# HammerHeadBreakout.net
KiCad netlist of a schematic drawn in Altium Designer
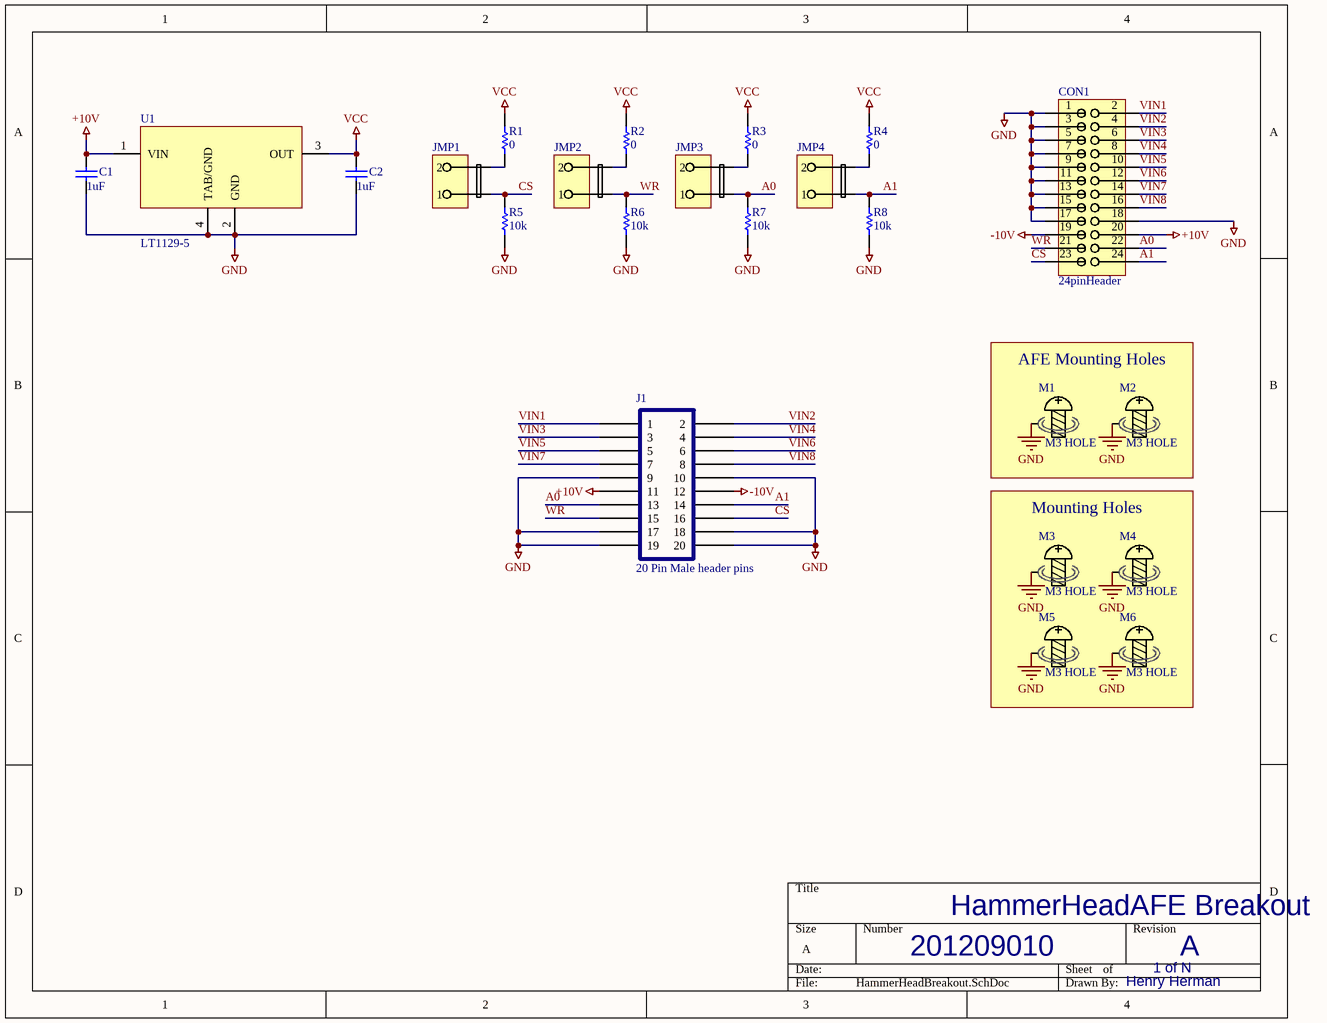
[diagram p0: HammerHeadBreakout.SchDoc]

(export (version "E")
  (design (tool "Eeschema 10.0.6"))
  (components
    (comp (ref "C1")
      (value "1uF")
      (footprint "SM/C_0805")
      (description "CAP")
      (libsource (lib "Henry1_20_2010") (part "CAP"))
    )
    (comp (ref "C2")
      (value "1uF")
      (footprint "SM/C_0805")
      (description "CAP")
      (libsource (lib "Henry1_20_2010") (part "CAP"))
    )
    (comp (ref "CON1")
      (value "24pinHeader")
      (footprint "CONN-RECEPT-24PIN")
      (libsource (lib "Henry1_20_2010") (part "24pinHeader"))
    )
    (comp (ref "J1")
      (value "20 Pin Male header pins")
      (footprint "M10x2-Shrouded")
      (description "Standard 20 Pin Ribbon Cable Connector")
      (libsource (lib "Henry1_20_2010") (part "M10x2-HeaderPinsConnector"))
    )
    (comp (ref "JMP1")
      (value "JMPR-2PIN-THRU")
      (footprint "M02")
      (libsource (lib "Henry1_20_2010") (part "JMPR-2PIN-THRU"))
    )
    (comp (ref "JMP2")
      (value "JMPR-2PIN-THRU")
      (footprint "M02")
      (libsource (lib "Henry1_20_2010") (part "JMPR-2PIN-THRU"))
    )
    (comp (ref "JMP3")
      (value "JMPR-2PIN-THRU")
      (footprint "M02")
      (libsource (lib "Henry1_20_2010") (part "JMPR-2PIN-THRU"))
    )
    (comp (ref "JMP4")
      (value "JMPR-2PIN-THRU")
      (footprint "M02")
      (libsource (lib "Henry1_20_2010") (part "JMPR-2PIN-THRU"))
    )
    (comp (ref "M1")
      (value "M3 HOLE")
      (footprint "MOUNTING_HOLE-125mil")
      (libsource (lib "Henry1_20_2010") (part "MountingHole"))
    )
    (comp (ref "M2")
      (value "M3 HOLE")
      (footprint "MOUNTING_HOLE-125mil")
      (libsource (lib "Henry1_20_2010") (part "MountingHole"))
    )
    (comp (ref "M3")
      (value "M3 HOLE")
      (footprint "MOUNTING_HOLE-125mil")
      (libsource (lib "Henry1_20_2010") (part "MountingHole"))
    )
    (comp (ref "M4")
      (value "M3 HOLE")
      (footprint "MOUNTING_HOLE-125mil")
      (libsource (lib "Henry1_20_2010") (part "MountingHole"))
    )
    (comp (ref "M5")
      (value "M3 HOLE")
      (footprint "MOUNTING_HOLE-125mil")
      (libsource (lib "Henry1_20_2010") (part "MountingHole"))
    )
    (comp (ref "M6")
      (value "M3 HOLE")
      (footprint "MOUNTING_HOLE-125mil")
      (libsource (lib "Henry1_20_2010") (part "MountingHole"))
    )
    (comp (ref "R1")
      (value "0")
      (footprint "SM/R_0805")
      (description "Resistor")
      (fields (field (name "Comment") "Res") (field (name "PUBLISHER") "Altium Limited"))
      (libsource (lib "Henry1_20_2010") (part "Res"))
    )
    (comp (ref "R2")
      (value "0")
      (footprint "SM/R_0805")
      (description "Resistor")
      (fields (field (name "Comment") "Res") (field (name "PUBLISHER") "Altium Limited"))
      (libsource (lib "Henry1_20_2010") (part "Res"))
    )
    (comp (ref "R3")
      (value "0")
      (footprint "SM/R_0805")
      (description "Resistor")
      (fields (field (name "Comment") "Res") (field (name "PUBLISHER") "Altium Limited"))
      (libsource (lib "Henry1_20_2010") (part "Res"))
    )
    (comp (ref "R4")
      (value "0")
      (footprint "SM/R_0805")
      (description "Resistor")
      (fields (field (name "Comment") "Res") (field (name "PUBLISHER") "Altium Limited"))
      (libsource (lib "Henry1_20_2010") (part "Res"))
    )
    (comp (ref "R5")
      (value "10k")
      (footprint "SM/R_0805")
      (description "Resistor")
      (fields (field (name "Comment") "Res") (field (name "PUBLISHER") "Altium Limited"))
      (libsource (lib "Henry1_20_2010") (part "Res"))
    )
    (comp (ref "R6")
      (value "10k")
      (footprint "SM/R_0805")
      (description "Resistor")
      (fields (field (name "Comment") "Res") (field (name "PUBLISHER") "Altium Limited"))
      (libsource (lib "Henry1_20_2010") (part "Res"))
    )
    (comp (ref "R7")
      (value "10k")
      (footprint "SM/R_0805")
      (description "Resistor")
      (fields (field (name "Comment") "Res") (field (name "PUBLISHER") "Altium Limited"))
      (libsource (lib "Henry1_20_2010") (part "Res"))
    )
    (comp (ref "R8")
      (value "10k")
      (footprint "SM/R_0805")
      (description "Resistor")
      (fields (field (name "Comment") "Res") (field (name "PUBLISHER") "Altium Limited"))
      (libsource (lib "Henry1_20_2010") (part "Res"))
    )
    (comp (ref "U1")
      (value "LT1129-5")
      (footprint "SOT223-3Lead-STPackage-LinearTechLT1129-3.3")
      (libsource (lib "Henry1_20_2010") (part "LT1129-5"))
    )
  )
  (nets
    (net (code "1") (name "+10V") (class "Default")
      (node (ref "C1") (pin "2") (pinfunction "2_2") (pintype "passive"))
      (node (ref "CON1") (pin "20") (pinfunction "20_20") (pintype "passive"))
      (node (ref "J1") (pin "11") (pinfunction "11_11") (pintype "passive"))
      (node (ref "U1") (pin "1") (pinfunction "VIN_1") (pintype "passive"))
    )
    (net (code "2") (name "-10V") (class "Default")
      (node (ref "CON1") (pin "19") (pinfunction "19_19") (pintype "passive"))
      (node (ref "J1") (pin "12") (pinfunction "12_12") (pintype "passive"))
    )
    (net (code "3") (name "/A0") (class "Default")
      (node (ref "CON1") (pin "22") (pinfunction "22_22") (pintype "passive"))
      (node (ref "J1") (pin "13") (pinfunction "13_13") (pintype "passive"))
      (node (ref "JMP3") (pin "1") (pinfunction "1_1") (pintype "passive"))
      (node (ref "R7") (pin "2") (pinfunction "2_2") (pintype "passive"))
    )
    (net (code "4") (name "/A1") (class "Default")
      (node (ref "CON1") (pin "24") (pinfunction "24_24") (pintype "passive"))
      (node (ref "J1") (pin "14") (pinfunction "14_14") (pintype "passive"))
      (node (ref "JMP4") (pin "1") (pinfunction "1_1") (pintype "passive"))
      (node (ref "R8") (pin "2") (pinfunction "2_2") (pintype "passive"))
    )
    (net (code "5") (name "/CS") (class "Default")
      (node (ref "CON1") (pin "23") (pinfunction "23_23") (pintype "passive"))
      (node (ref "J1") (pin "16") (pinfunction "16_16") (pintype "passive"))
      (node (ref "JMP1") (pin "1") (pinfunction "1_1") (pintype "passive"))
      (node (ref "R5") (pin "2") (pinfunction "2_2") (pintype "passive"))
    )
    (net (code "6") (name "/VIN1") (class "Default")
      (node (ref "CON1") (pin "2") (pinfunction "2_2") (pintype "passive"))
      (node (ref "J1") (pin "1") (pinfunction "1_1") (pintype "passive"))
    )
    (net (code "7") (name "/VIN2") (class "Default")
      (node (ref "CON1") (pin "4") (pinfunction "4_4") (pintype "passive"))
      (node (ref "J1") (pin "2") (pinfunction "2_2") (pintype "passive"))
    )
    (net (code "8") (name "/VIN3") (class "Default")
      (node (ref "CON1") (pin "6") (pinfunction "6_6") (pintype "passive"))
      (node (ref "J1") (pin "3") (pinfunction "3_3") (pintype "passive"))
    )
    (net (code "9") (name "/VIN4") (class "Default")
      (node (ref "CON1") (pin "8") (pinfunction "8_8") (pintype "passive"))
      (node (ref "J1") (pin "4") (pinfunction "4_4") (pintype "passive"))
    )
    (net (code "10") (name "/VIN5") (class "Default")
      (node (ref "CON1") (pin "10") (pinfunction "10_10") (pintype "passive"))
      (node (ref "J1") (pin "5") (pinfunction "5_5") (pintype "passive"))
    )
    (net (code "11") (name "/VIN6") (class "Default")
      (node (ref "CON1") (pin "12") (pinfunction "12_12") (pintype "passive"))
      (node (ref "J1") (pin "6") (pinfunction "6_6") (pintype "passive"))
    )
    (net (code "12") (name "/VIN7") (class "Default")
      (node (ref "CON1") (pin "14") (pinfunction "14_14") (pintype "passive"))
      (node (ref "J1") (pin "7") (pinfunction "7_7") (pintype "passive"))
    )
    (net (code "13") (name "/VIN8") (class "Default")
      (node (ref "CON1") (pin "16") (pinfunction "16_16") (pintype "passive"))
      (node (ref "J1") (pin "8") (pinfunction "8_8") (pintype "passive"))
    )
    (net (code "14") (name "/WR") (class "Default")
      (node (ref "CON1") (pin "21") (pinfunction "21_21") (pintype "passive"))
      (node (ref "J1") (pin "15") (pinfunction "15_15") (pintype "passive"))
      (node (ref "JMP2") (pin "1") (pinfunction "1_1") (pintype "passive"))
      (node (ref "R6") (pin "2") (pinfunction "2_2") (pintype "passive"))
    )
    (net (code "15") (name "GND") (class "Default")
      (node (ref "C1") (pin "1") (pinfunction "1_1") (pintype "passive"))
      (node (ref "C2") (pin "1") (pinfunction "1_1") (pintype "passive"))
      (node (ref "CON1") (pin "1") (pinfunction "1_1") (pintype "passive"))
      (node (ref "CON1") (pin "11") (pinfunction "11_11") (pintype "passive"))
      (node (ref "CON1") (pin "13") (pinfunction "13_13") (pintype "passive"))
      (node (ref "CON1") (pin "15") (pinfunction "15_15") (pintype "passive"))
      (node (ref "CON1") (pin "17") (pinfunction "17_17") (pintype "passive"))
      (node (ref "CON1") (pin "18") (pinfunction "18_18") (pintype "passive"))
      (node (ref "CON1") (pin "3") (pinfunction "3_3") (pintype "passive"))
      (node (ref "CON1") (pin "5") (pinfunction "5_5") (pintype "passive"))
      (node (ref "CON1") (pin "7") (pinfunction "7_7") (pintype "passive"))
      (node (ref "CON1") (pin "9") (pinfunction "9_9") (pintype "passive"))
      (node (ref "J1") (pin "10") (pinfunction "10_10") (pintype "passive"))
      (node (ref "J1") (pin "17") (pinfunction "17_17") (pintype "passive"))
      (node (ref "J1") (pin "18") (pinfunction "18_18") (pintype "passive"))
      (node (ref "J1") (pin "19") (pinfunction "19_19") (pintype "passive"))
      (node (ref "J1") (pin "20") (pinfunction "20_20") (pintype "passive"))
      (node (ref "J1") (pin "9") (pinfunction "9_9") (pintype "passive"))
      (node (ref "M1") (pin "0") (pinfunction "PAD_0") (pintype "power_in"))
      (node (ref "M2") (pin "0") (pinfunction "PAD_0") (pintype "power_in"))
      (node (ref "M3") (pin "0") (pinfunction "PAD_0") (pintype "power_in"))
      (node (ref "M4") (pin "0") (pinfunction "PAD_0") (pintype "power_in"))
      (node (ref "M5") (pin "0") (pinfunction "PAD_0") (pintype "power_in"))
      (node (ref "M6") (pin "0") (pinfunction "PAD_0") (pintype "power_in"))
      (node (ref "R5") (pin "1") (pinfunction "1_1") (pintype "passive"))
      (node (ref "R6") (pin "1") (pinfunction "1_1") (pintype "passive"))
      (node (ref "R7") (pin "1") (pinfunction "1_1") (pintype "passive"))
      (node (ref "R8") (pin "1") (pinfunction "1_1") (pintype "passive"))
      (node (ref "U1") (pin "2") (pinfunction "GND_2") (pintype "passive"))
      (node (ref "U1") (pin "4") (pinfunction "TAB/GND_4") (pintype "passive"))
    )
    (net (code "16") (name "Net-(JMP1-Pad2)") (class "Default")
      (node (ref "JMP1") (pin "2") (pinfunction "2_2") (pintype "passive"))
      (node (ref "R1") (pin "1") (pinfunction "1_1") (pintype "passive"))
    )
    (net (code "17") (name "Net-(JMP2-Pad2)") (class "Default")
      (node (ref "JMP2") (pin "2") (pinfunction "2_2") (pintype "passive"))
      (node (ref "R2") (pin "1") (pinfunction "1_1") (pintype "passive"))
    )
    (net (code "18") (name "Net-(JMP3-Pad2)") (class "Default")
      (node (ref "JMP3") (pin "2") (pinfunction "2_2") (pintype "passive"))
      (node (ref "R3") (pin "1") (pinfunction "1_1") (pintype "passive"))
    )
    (net (code "19") (name "Net-(JMP4-Pad2)") (class "Default")
      (node (ref "JMP4") (pin "2") (pinfunction "2_2") (pintype "passive"))
      (node (ref "R4") (pin "1") (pinfunction "1_1") (pintype "passive"))
    )
    (net (code "20") (name "VCC") (class "Default")
      (node (ref "C2") (pin "2") (pinfunction "2_2") (pintype "passive"))
      (node (ref "R1") (pin "2") (pinfunction "2_2") (pintype "passive"))
      (node (ref "R2") (pin "2") (pinfunction "2_2") (pintype "passive"))
      (node (ref "R3") (pin "2") (pinfunction "2_2") (pintype "passive"))
      (node (ref "R4") (pin "2") (pinfunction "2_2") (pintype "passive"))
      (node (ref "U1") (pin "3") (pinfunction "OUT_3") (pintype "passive"))
    )
  )
)
